# XPDR_Board_1.net
KiCad netlist of a schematic drawn in EAGLE
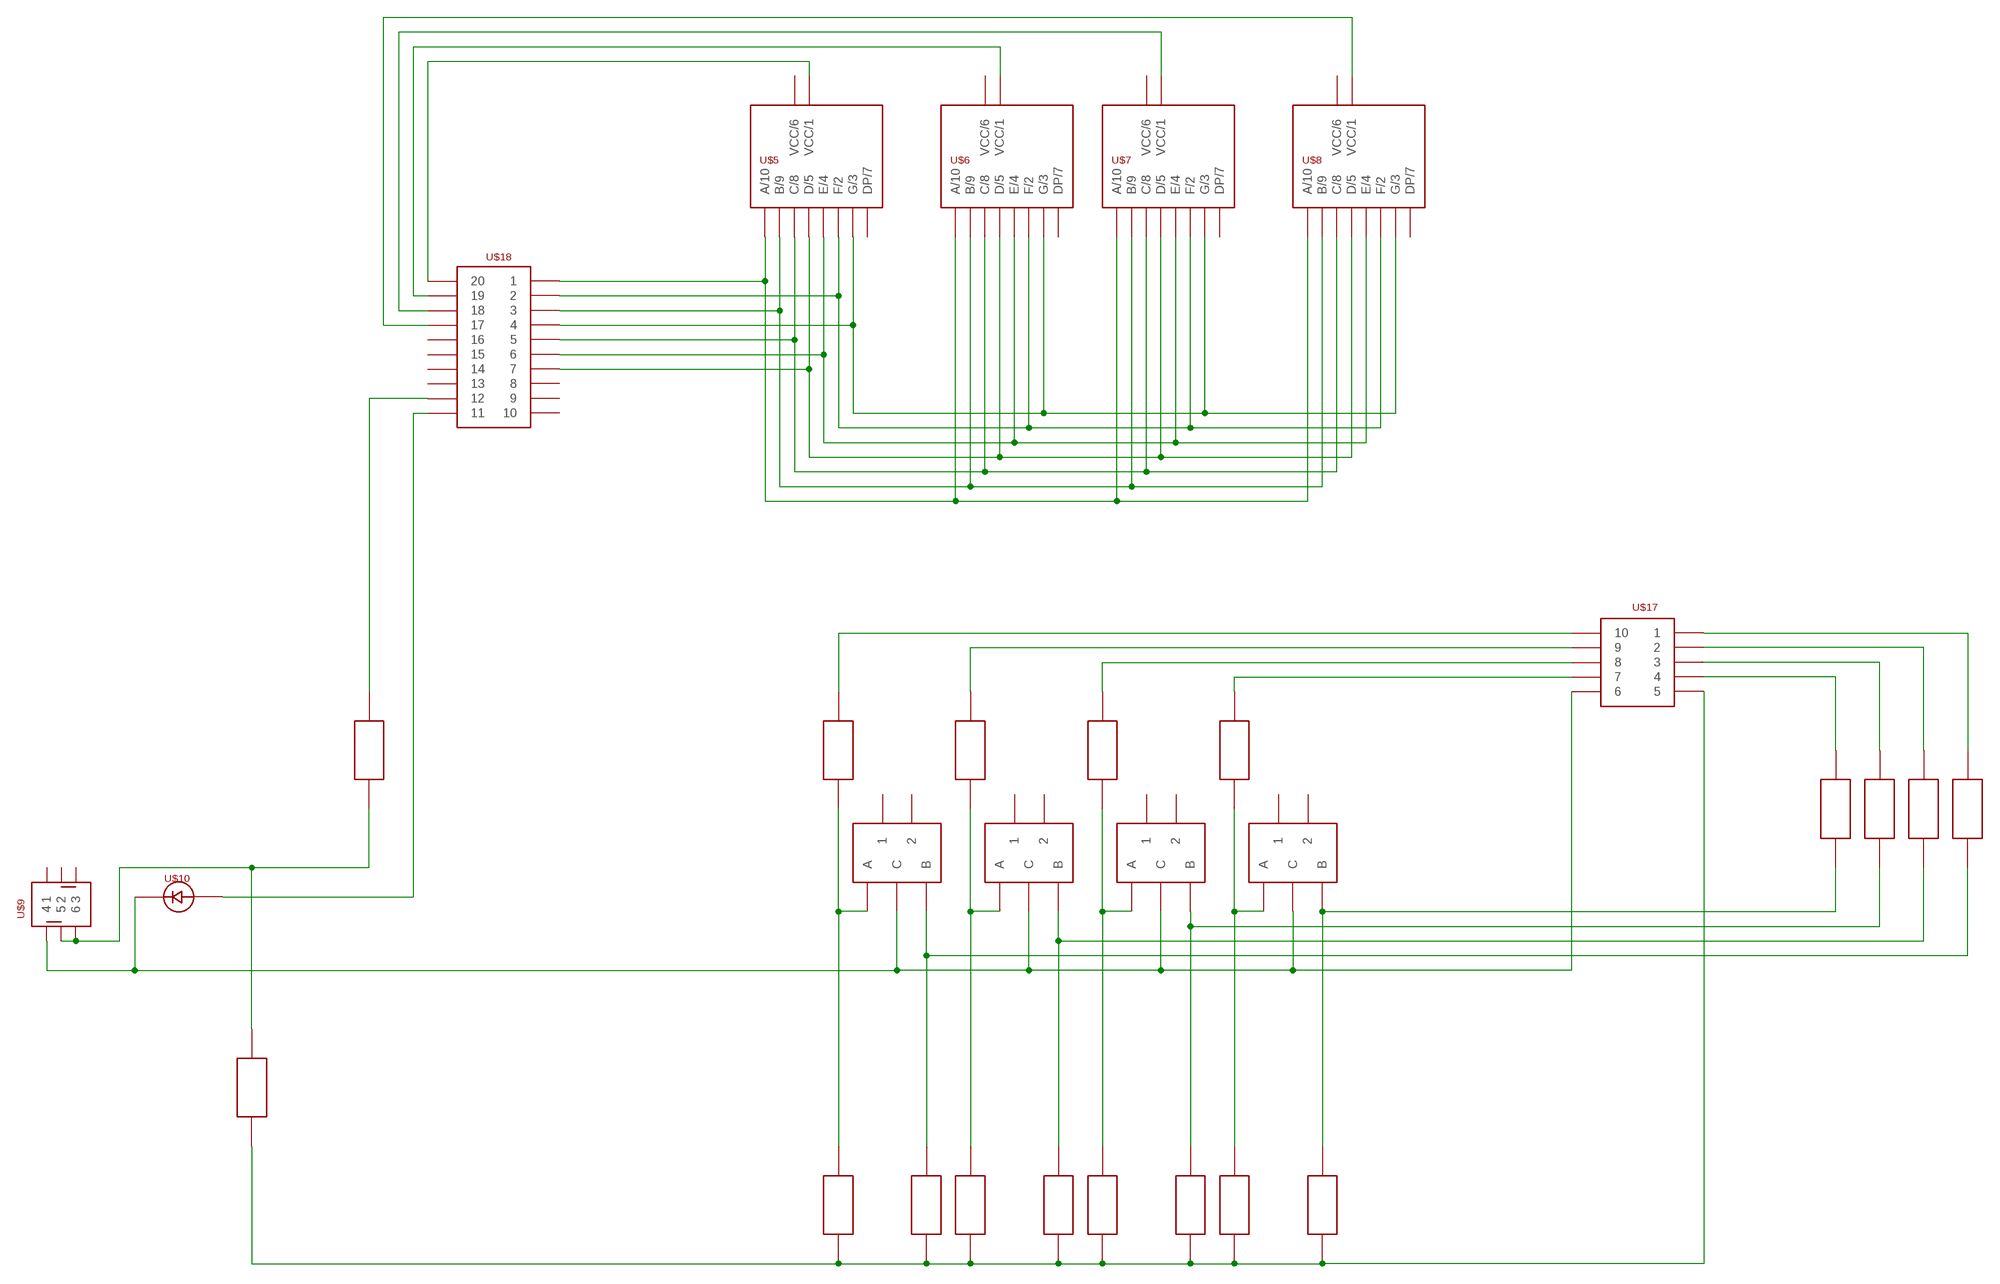
[diagram p0: schematic, sheet 1]

(export (version "E")
  (design (tool "Eeschema 10.0.6"))
  (components
    (comp (ref "U$1")
      (value "PEC11R")
      (footprint "eagle-import:PEC11R")
      (libsource (lib "eagle-import") (part "PEC11R"))
    )
    (comp (ref "U$2")
      (value "PEC11R")
      (footprint "eagle-import:PEC11R")
      (libsource (lib "eagle-import") (part "PEC11R"))
    )
    (comp (ref "U$3")
      (value "PEC11R")
      (footprint "eagle-import:PEC11R")
      (libsource (lib "eagle-import") (part "PEC11R"))
    )
    (comp (ref "U$4")
      (value "PEC11R")
      (footprint "eagle-import:PEC11R")
      (libsource (lib "eagle-import") (part "PEC11R"))
    )
    (comp (ref "U$5")
      (value "SA3611EWA")
      (footprint "eagle-import:SA3611EWA")
      (libsource (lib "eagle-import") (part "SA3611EWA"))
    )
    (comp (ref "U$6")
      (value "SA3611EWA")
      (footprint "eagle-import:SA3611EWA")
      (libsource (lib "eagle-import") (part "SA3611EWA"))
    )
    (comp (ref "U$7")
      (value "SA3611EWA")
      (footprint "eagle-import:SA3611EWA")
      (libsource (lib "eagle-import") (part "SA3611EWA"))
    )
    (comp (ref "U$8")
      (value "SA3611EWA")
      (footprint "eagle-import:SA3611EWA")
      (libsource (lib "eagle-import") (part "SA3611EWA"))
    )
    (comp (ref "U$9")
      (value "P1-0S")
      (footprint "eagle-import:P1-0S")
      (libsource (lib "eagle-import") (part "P1-0S"))
    )
    (comp (ref "U$10")
      (value "LED_5MM")
      (footprint "eagle-import:LED_5MM")
      (libsource (lib "eagle-import") (part "LED_5MM"))
    )
    (comp (ref "U$11")
      (value "REZISTOR")
      (footprint "eagle-import:REZISTOR")
      (libsource (lib "eagle-import") (part "REZISTOR"))
    )
    (comp (ref "U$12")
      (value "REZISTOR")
      (footprint "eagle-import:REZISTOR")
      (libsource (lib "eagle-import") (part "REZISTOR"))
    )
    (comp (ref "U$13")
      (value "REZISTOR")
      (footprint "eagle-import:REZISTOR")
      (libsource (lib "eagle-import") (part "REZISTOR"))
    )
    (comp (ref "U$14")
      (value "REZISTOR")
      (footprint "eagle-import:REZISTOR")
      (libsource (lib "eagle-import") (part "REZISTOR"))
    )
    (comp (ref "U$15")
      (value "REZISTOR")
      (footprint "eagle-import:REZISTOR")
      (libsource (lib "eagle-import") (part "REZISTOR"))
    )
    (comp (ref "U$16")
      (value "REZISTOR")
      (footprint "eagle-import:REZISTOR")
      (libsource (lib "eagle-import") (part "REZISTOR"))
    )
    (comp (ref "U$17")
      (value "LISTA_2X5")
      (footprint "eagle-import:LISTA_2X5")
      (libsource (lib "eagle-import") (part "LISTA_2X5"))
    )
    (comp (ref "U$18")
      (value "LISTA_2X10")
      (footprint "eagle-import:LISTA_2X10")
      (libsource (lib "eagle-import") (part "LISTA_2X10"))
    )
    (comp (ref "U$19")
      (value "REZISTOR")
      (footprint "eagle-import:REZISTOR")
      (libsource (lib "eagle-import") (part "REZISTOR"))
    )
    (comp (ref "U$20")
      (value "REZISTOR")
      (footprint "eagle-import:REZISTOR")
      (libsource (lib "eagle-import") (part "REZISTOR"))
    )
    (comp (ref "U$21")
      (value "REZISTOR")
      (footprint "eagle-import:REZISTOR")
      (libsource (lib "eagle-import") (part "REZISTOR"))
    )
    (comp (ref "U$22")
      (value "REZISTOR")
      (footprint "eagle-import:REZISTOR")
      (libsource (lib "eagle-import") (part "REZISTOR"))
    )
    (comp (ref "U$23")
      (value "REZISTOR")
      (footprint "eagle-import:REZISTOR")
      (libsource (lib "eagle-import") (part "REZISTOR"))
    )
    (comp (ref "U$24")
      (value "REZISTOR")
      (footprint "eagle-import:REZISTOR")
      (libsource (lib "eagle-import") (part "REZISTOR"))
    )
    (comp (ref "U$25")
      (value "REZISTOR")
      (footprint "eagle-import:REZISTOR")
      (libsource (lib "eagle-import") (part "REZISTOR"))
    )
    (comp (ref "U$26")
      (value "REZISTOR")
      (footprint "eagle-import:REZISTOR")
      (libsource (lib "eagle-import") (part "REZISTOR"))
    )
    (comp (ref "U$27")
      (value "REZISTOR")
      (footprint "eagle-import:REZISTOR")
      (libsource (lib "eagle-import") (part "REZISTOR"))
    )
    (comp (ref "U$28")
      (value "REZISTOR")
      (footprint "eagle-import:REZISTOR")
      (libsource (lib "eagle-import") (part "REZISTOR"))
    )
    (comp (ref "U$30")
      (value "REZISTOR")
      (footprint "eagle-import:REZISTOR")
      (libsource (lib "eagle-import") (part "REZISTOR"))
    )
    (comp (ref "U$31")
      (value "REZISTOR")
      (footprint "eagle-import:REZISTOR")
      (libsource (lib "eagle-import") (part "REZISTOR"))
    )
  )
  (nets
    (net (code "1") (name "Net-(U$1-PadA)") (class "Default")
      (node (ref "U$1") (pin "A") (pinfunction "A_A") (pintype "bidirectional"))
      (node (ref "U$11") (pin "P$1") (pinfunction "P$1_P$1") (pintype "bidirectional"))
      (node (ref "U$28") (pin "P$1") (pinfunction "P$1_P$1") (pintype "bidirectional"))
    )
    (net (code "2") (name "Net-(U$1-PadB)") (class "Default")
      (node (ref "U$1") (pin "B") (pinfunction "B_B") (pintype "bidirectional"))
      (node (ref "U$12") (pin "P$1") (pinfunction "P$1_P$1") (pintype "bidirectional"))
      (node (ref "U$27") (pin "P$1") (pinfunction "P$1_P$1") (pintype "bidirectional"))
    )
    (net (code "3") (name "Net-(U$1-PadC)") (class "Default")
      (node (ref "U$1") (pin "C") (pinfunction "C_C") (pintype "bidirectional"))
      (node (ref "U$10") (pin "P$2") (pinfunction "P$2_P$2") (pintype "bidirectional"))
      (node (ref "U$17") (pin "6") (pinfunction "6_6") (pintype "bidirectional"))
      (node (ref "U$2") (pin "C") (pinfunction "C_C") (pintype "bidirectional"))
      (node (ref "U$3") (pin "C") (pinfunction "C_C") (pintype "bidirectional"))
      (node (ref "U$4") (pin "C") (pinfunction "C_C") (pintype "bidirectional"))
      (node (ref "U$9") (pin "4") (pinfunction "4_4") (pintype "bidirectional"))
    )
    (net (code "4") (name "Net-(U$5-A{slash}10)") (class "Default")
      (node (ref "U$18") (pin "1") (pinfunction "1_1") (pintype "bidirectional"))
      (node (ref "U$5") (pin "10") (pinfunction "A/10_10") (pintype "bidirectional"))
      (node (ref "U$6") (pin "10") (pinfunction "A/10_10") (pintype "bidirectional"))
      (node (ref "U$7") (pin "10") (pinfunction "A/10_10") (pintype "bidirectional"))
      (node (ref "U$8") (pin "10") (pinfunction "A/10_10") (pintype "bidirectional"))
    )
    (net (code "5") (name "Net-(U$5-B{slash}9)") (class "Default")
      (node (ref "U$18") (pin "3") (pinfunction "3_3") (pintype "bidirectional"))
      (node (ref "U$5") (pin "9") (pinfunction "B/9_9") (pintype "bidirectional"))
      (node (ref "U$6") (pin "9") (pinfunction "B/9_9") (pintype "bidirectional"))
      (node (ref "U$7") (pin "9") (pinfunction "B/9_9") (pintype "bidirectional"))
      (node (ref "U$8") (pin "9") (pinfunction "B/9_9") (pintype "bidirectional"))
    )
    (net (code "6") (name "Net-(U$5-C{slash}8)") (class "Default")
      (node (ref "U$18") (pin "5") (pinfunction "5_5") (pintype "bidirectional"))
      (node (ref "U$5") (pin "8") (pinfunction "C/8_8") (pintype "bidirectional"))
      (node (ref "U$6") (pin "8") (pinfunction "C/8_8") (pintype "bidirectional"))
      (node (ref "U$7") (pin "8") (pinfunction "C/8_8") (pintype "bidirectional"))
      (node (ref "U$8") (pin "8") (pinfunction "C/8_8") (pintype "bidirectional"))
    )
    (net (code "7") (name "Net-(U$5-D{slash}5)") (class "Default")
      (node (ref "U$18") (pin "7") (pinfunction "7_7") (pintype "bidirectional"))
      (node (ref "U$5") (pin "5") (pinfunction "D/5_5") (pintype "bidirectional"))
      (node (ref "U$6") (pin "5") (pinfunction "D/5_5") (pintype "bidirectional"))
      (node (ref "U$7") (pin "5") (pinfunction "D/5_5") (pintype "bidirectional"))
      (node (ref "U$8") (pin "5") (pinfunction "D/5_5") (pintype "bidirectional"))
    )
    (net (code "8") (name "Net-(U$5-E{slash}4)") (class "Default")
      (node (ref "U$18") (pin "6") (pinfunction "6_6") (pintype "bidirectional"))
      (node (ref "U$5") (pin "4") (pinfunction "E/4_4") (pintype "bidirectional"))
      (node (ref "U$6") (pin "4") (pinfunction "E/4_4") (pintype "bidirectional"))
      (node (ref "U$7") (pin "4") (pinfunction "E/4_4") (pintype "bidirectional"))
      (node (ref "U$8") (pin "4") (pinfunction "E/4_4") (pintype "bidirectional"))
    )
    (net (code "9") (name "Net-(U$5-F{slash}2)") (class "Default")
      (node (ref "U$18") (pin "2") (pinfunction "2_2") (pintype "bidirectional"))
      (node (ref "U$5") (pin "2") (pinfunction "F/2_2") (pintype "bidirectional"))
      (node (ref "U$6") (pin "2") (pinfunction "F/2_2") (pintype "bidirectional"))
      (node (ref "U$7") (pin "2") (pinfunction "F/2_2") (pintype "bidirectional"))
      (node (ref "U$8") (pin "2") (pinfunction "F/2_2") (pintype "bidirectional"))
    )
    (net (code "10") (name "Net-(U$5-G{slash}3)") (class "Default")
      (node (ref "U$18") (pin "4") (pinfunction "4_4") (pintype "bidirectional"))
      (node (ref "U$5") (pin "3") (pinfunction "G/3_3") (pintype "bidirectional"))
      (node (ref "U$6") (pin "3") (pinfunction "G/3_3") (pintype "bidirectional"))
      (node (ref "U$7") (pin "3") (pinfunction "G/3_3") (pintype "bidirectional"))
      (node (ref "U$8") (pin "3") (pinfunction "G/3_3") (pintype "bidirectional"))
    )
    (net (code "11") (name "Net-(U$5-VCC{slash}1)") (class "Default")
      (node (ref "U$18") (pin "20") (pinfunction "20_20") (pintype "bidirectional"))
      (node (ref "U$5") (pin "1") (pinfunction "VCC/1_1") (pintype "bidirectional"))
    )
    (net (code "12") (name "Net-(U$6-VCC{slash}1)") (class "Default")
      (node (ref "U$18") (pin "19") (pinfunction "19_19") (pintype "bidirectional"))
      (node (ref "U$6") (pin "1") (pinfunction "VCC/1_1") (pintype "bidirectional"))
    )
    (net (code "13") (name "Net-(U$7-VCC{slash}1)") (class "Default")
      (node (ref "U$18") (pin "18") (pinfunction "18_18") (pintype "bidirectional"))
      (node (ref "U$7") (pin "1") (pinfunction "VCC/1_1") (pintype "bidirectional"))
    )
    (net (code "14") (name "Net-(U$8-VCC{slash}1)") (class "Default")
      (node (ref "U$18") (pin "17") (pinfunction "17_17") (pintype "bidirectional"))
      (node (ref "U$8") (pin "1") (pinfunction "VCC/1_1") (pintype "bidirectional"))
    )
    (net (code "15") (name "Net-(U$10-PadP$1)") (class "Default")
      (node (ref "U$10") (pin "P$1") (pinfunction "P$1_P$1") (pintype "bidirectional"))
      (node (ref "U$18") (pin "11") (pinfunction "11_11") (pintype "bidirectional"))
    )
    (net (code "16") (name "Net-(U$11-PadP$2)") (class "Default")
      (node (ref "U$11") (pin "P$2") (pinfunction "P$2_P$2") (pintype "bidirectional"))
      (node (ref "U$17") (pin "10") (pinfunction "10_10") (pintype "bidirectional"))
    )
    (net (code "17") (name "Net-(U$12-PadP$2)") (class "Default")
      (node (ref "U$12") (pin "P$2") (pinfunction "P$2_P$2") (pintype "bidirectional"))
      (node (ref "U$17") (pin "1") (pinfunction "1_1") (pintype "bidirectional"))
    )
    (net (code "18") (name "Net-(U$13-PadP$1)") (class "Default")
      (node (ref "U$13") (pin "P$1") (pinfunction "P$1_P$1") (pintype "bidirectional"))
      (node (ref "U$2") (pin "A") (pinfunction "A_A") (pintype "bidirectional"))
      (node (ref "U$26") (pin "P$1") (pinfunction "P$1_P$1") (pintype "bidirectional"))
    )
    (net (code "19") (name "Net-(U$13-PadP$2)") (class "Default")
      (node (ref "U$13") (pin "P$2") (pinfunction "P$2_P$2") (pintype "bidirectional"))
      (node (ref "U$17") (pin "9") (pinfunction "9_9") (pintype "bidirectional"))
    )
    (net (code "20") (name "Net-(U$14-PadP$1)") (class "Default")
      (node (ref "U$14") (pin "P$1") (pinfunction "P$1_P$1") (pintype "bidirectional"))
      (node (ref "U$2") (pin "B") (pinfunction "B_B") (pintype "bidirectional"))
      (node (ref "U$25") (pin "P$1") (pinfunction "P$1_P$1") (pintype "bidirectional"))
    )
    (net (code "21") (name "Net-(U$14-PadP$2)") (class "Default")
      (node (ref "U$14") (pin "P$2") (pinfunction "P$2_P$2") (pintype "bidirectional"))
      (node (ref "U$17") (pin "2") (pinfunction "2_2") (pintype "bidirectional"))
    )
    (net (code "22") (name "Net-(U$15-PadP$1)") (class "Default")
      (node (ref "U$15") (pin "P$1") (pinfunction "P$1_P$1") (pintype "bidirectional"))
      (node (ref "U$24") (pin "P$1") (pinfunction "P$1_P$1") (pintype "bidirectional"))
      (node (ref "U$3") (pin "A") (pinfunction "A_A") (pintype "bidirectional"))
    )
    (net (code "23") (name "Net-(U$15-PadP$2)") (class "Default")
      (node (ref "U$15") (pin "P$2") (pinfunction "P$2_P$2") (pintype "bidirectional"))
      (node (ref "U$17") (pin "8") (pinfunction "8_8") (pintype "bidirectional"))
    )
    (net (code "24") (name "Net-(U$16-PadP$1)") (class "Default")
      (node (ref "U$16") (pin "P$1") (pinfunction "P$1_P$1") (pintype "bidirectional"))
      (node (ref "U$23") (pin "P$1") (pinfunction "P$1_P$1") (pintype "bidirectional"))
      (node (ref "U$3") (pin "B") (pinfunction "B_B") (pintype "bidirectional"))
    )
    (net (code "25") (name "Net-(U$16-PadP$2)") (class "Default")
      (node (ref "U$16") (pin "P$2") (pinfunction "P$2_P$2") (pintype "bidirectional"))
      (node (ref "U$17") (pin "3") (pinfunction "3_3") (pintype "bidirectional"))
    )
    (net (code "26") (name "Net-(U$17-Pad4)") (class "Default")
      (node (ref "U$17") (pin "4") (pinfunction "4_4") (pintype "bidirectional"))
      (node (ref "U$20") (pin "P$2") (pinfunction "P$2_P$2") (pintype "bidirectional"))
    )
    (net (code "27") (name "Net-(U$17-Pad5)") (class "Default")
      (node (ref "U$17") (pin "5") (pinfunction "5_5") (pintype "bidirectional"))
      (node (ref "U$21") (pin "P$2") (pinfunction "P$2_P$2") (pintype "bidirectional"))
      (node (ref "U$22") (pin "P$2") (pinfunction "P$2_P$2") (pintype "bidirectional"))
      (node (ref "U$23") (pin "P$2") (pinfunction "P$2_P$2") (pintype "bidirectional"))
      (node (ref "U$24") (pin "P$2") (pinfunction "P$2_P$2") (pintype "bidirectional"))
      (node (ref "U$25") (pin "P$2") (pinfunction "P$2_P$2") (pintype "bidirectional"))
      (node (ref "U$26") (pin "P$2") (pinfunction "P$2_P$2") (pintype "bidirectional"))
      (node (ref "U$27") (pin "P$2") (pinfunction "P$2_P$2") (pintype "bidirectional"))
      (node (ref "U$28") (pin "P$2") (pinfunction "P$2_P$2") (pintype "bidirectional"))
      (node (ref "U$31") (pin "P$2") (pinfunction "P$2_P$2") (pintype "bidirectional"))
    )
    (net (code "28") (name "Net-(U$17-Pad7)") (class "Default")
      (node (ref "U$17") (pin "7") (pinfunction "7_7") (pintype "bidirectional"))
      (node (ref "U$19") (pin "P$2") (pinfunction "P$2_P$2") (pintype "bidirectional"))
    )
    (net (code "29") (name "Net-(U$18-Pad12)") (class "Default")
      (node (ref "U$18") (pin "12") (pinfunction "12_12") (pintype "bidirectional"))
      (node (ref "U$30") (pin "P$1") (pinfunction "P$1_P$1") (pintype "bidirectional"))
    )
    (net (code "30") (name "Net-(U$19-PadP$1)") (class "Default")
      (node (ref "U$19") (pin "P$1") (pinfunction "P$1_P$1") (pintype "bidirectional"))
      (node (ref "U$22") (pin "P$1") (pinfunction "P$1_P$1") (pintype "bidirectional"))
      (node (ref "U$4") (pin "A") (pinfunction "A_A") (pintype "bidirectional"))
    )
    (net (code "31") (name "Net-(U$20-PadP$1)") (class "Default")
      (node (ref "U$20") (pin "P$1") (pinfunction "P$1_P$1") (pintype "bidirectional"))
      (node (ref "U$21") (pin "P$1") (pinfunction "P$1_P$1") (pintype "bidirectional"))
      (node (ref "U$4") (pin "B") (pinfunction "B_B") (pintype "bidirectional"))
    )
    (net (code "32") (name "Net-(U$30-PadP$2)") (class "Default")
      (node (ref "U$30") (pin "P$2") (pinfunction "P$2_P$2") (pintype "bidirectional"))
      (node (ref "U$31") (pin "P$1") (pinfunction "P$1_P$1") (pintype "bidirectional"))
      (node (ref "U$9") (pin "5") (pinfunction "5_5") (pintype "bidirectional"))
      (node (ref "U$9") (pin "6") (pinfunction "6_6") (pintype "bidirectional"))
    )
    (net (code "33") (name "unconnected-(U$1-Pad1)") (class "Default")
      (node (ref "U$1") (pin "1") (pinfunction "1_1") (pintype "bidirectional"))
    )
    (net (code "34") (name "unconnected-(U$1-Pad2)") (class "Default")
      (node (ref "U$1") (pin "2") (pinfunction "2_2") (pintype "bidirectional"))
    )
    (net (code "35") (name "unconnected-(U$2-Pad1)") (class "Default")
      (node (ref "U$2") (pin "1") (pinfunction "1_1") (pintype "bidirectional"))
    )
    (net (code "36") (name "unconnected-(U$2-Pad2)") (class "Default")
      (node (ref "U$2") (pin "2") (pinfunction "2_2") (pintype "bidirectional"))
    )
    (net (code "37") (name "unconnected-(U$3-Pad1)") (class "Default")
      (node (ref "U$3") (pin "1") (pinfunction "1_1") (pintype "bidirectional"))
    )
    (net (code "38") (name "unconnected-(U$3-Pad2)") (class "Default")
      (node (ref "U$3") (pin "2") (pinfunction "2_2") (pintype "bidirectional"))
    )
    (net (code "39") (name "unconnected-(U$4-Pad1)") (class "Default")
      (node (ref "U$4") (pin "1") (pinfunction "1_1") (pintype "bidirectional"))
    )
    (net (code "40") (name "unconnected-(U$4-Pad2)") (class "Default")
      (node (ref "U$4") (pin "2") (pinfunction "2_2") (pintype "bidirectional"))
    )
    (net (code "41") (name "unconnected-(U$5-DP{slash}7-Pad7)") (class "Default")
      (node (ref "U$5") (pin "7") (pinfunction "DP/7_7") (pintype "bidirectional"))
    )
    (net (code "42") (name "unconnected-(U$5-VCC{slash}6-Pad6)") (class "Default")
      (node (ref "U$5") (pin "6") (pinfunction "VCC/6_6") (pintype "bidirectional"))
    )
    (net (code "43") (name "unconnected-(U$6-DP{slash}7-Pad7)") (class "Default")
      (node (ref "U$6") (pin "7") (pinfunction "DP/7_7") (pintype "bidirectional"))
    )
    (net (code "44") (name "unconnected-(U$6-VCC{slash}6-Pad6)") (class "Default")
      (node (ref "U$6") (pin "6") (pinfunction "VCC/6_6") (pintype "bidirectional"))
    )
    (net (code "45") (name "unconnected-(U$7-DP{slash}7-Pad7)") (class "Default")
      (node (ref "U$7") (pin "7") (pinfunction "DP/7_7") (pintype "bidirectional"))
    )
    (net (code "46") (name "unconnected-(U$7-VCC{slash}6-Pad6)") (class "Default")
      (node (ref "U$7") (pin "6") (pinfunction "VCC/6_6") (pintype "bidirectional"))
    )
    (net (code "47") (name "unconnected-(U$8-DP{slash}7-Pad7)") (class "Default")
      (node (ref "U$8") (pin "7") (pinfunction "DP/7_7") (pintype "bidirectional"))
    )
    (net (code "48") (name "unconnected-(U$8-VCC{slash}6-Pad6)") (class "Default")
      (node (ref "U$8") (pin "6") (pinfunction "VCC/6_6") (pintype "bidirectional"))
    )
    (net (code "49") (name "unconnected-(U$9-Pad1)") (class "Default")
      (node (ref "U$9") (pin "1") (pinfunction "1_1") (pintype "bidirectional"))
    )
    (net (code "50") (name "unconnected-(U$9-Pad2)") (class "Default")
      (node (ref "U$9") (pin "2") (pinfunction "2_2") (pintype "bidirectional"))
    )
    (net (code "51") (name "unconnected-(U$9-Pad3)") (class "Default")
      (node (ref "U$9") (pin "3") (pinfunction "3_3") (pintype "bidirectional"))
    )
    (net (code "52") (name "unconnected-(U$18-Pad8)") (class "Default")
      (node (ref "U$18") (pin "8") (pinfunction "8_8") (pintype "bidirectional"))
    )
    (net (code "53") (name "unconnected-(U$18-Pad9)") (class "Default")
      (node (ref "U$18") (pin "9") (pinfunction "9_9") (pintype "bidirectional"))
    )
    (net (code "54") (name "unconnected-(U$18-Pad10)") (class "Default")
      (node (ref "U$18") (pin "10") (pinfunction "10_10") (pintype "bidirectional"))
    )
    (net (code "55") (name "unconnected-(U$18-Pad13)") (class "Default")
      (node (ref "U$18") (pin "13") (pinfunction "13_13") (pintype "bidirectional"))
    )
    (net (code "56") (name "unconnected-(U$18-Pad14)") (class "Default")
      (node (ref "U$18") (pin "14") (pinfunction "14_14") (pintype "bidirectional"))
    )
    (net (code "57") (name "unconnected-(U$18-Pad15)") (class "Default")
      (node (ref "U$18") (pin "15") (pinfunction "15_15") (pintype "bidirectional"))
    )
    (net (code "58") (name "unconnected-(U$18-Pad16)") (class "Default")
      (node (ref "U$18") (pin "16") (pinfunction "16_16") (pintype "bidirectional"))
    )
  )
)
